# MDB.net
KiCad netlist of a schematic drawn in Altium Designer
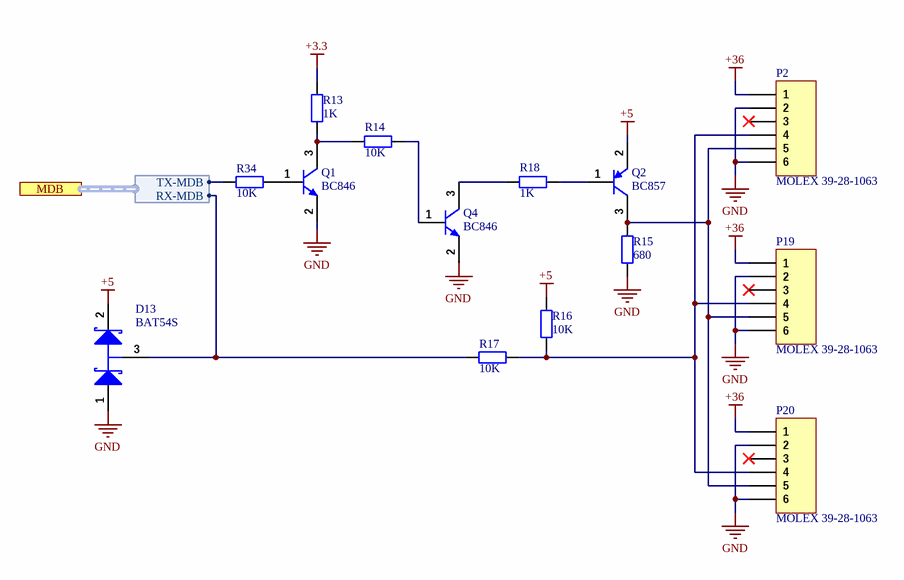
[diagram p0: MDB.SchDoc]

(export (version "E")
  (design (tool "Eeschema 10.0.6"))
  (components
    (comp (ref "D13")
      (value "BAT54S")
      (footprint "SOT23")
      (description "Schottky Barrier Double Diode")
      (fields (field (name "MANUFACTURER") "MULTICOMP"))
      (libsource (lib "Ares") (part "BAT54S"))
    )
    (comp (ref "P2")
      (value "MOLEX 39-28-1063")
      (footprint "MOLEX 39-28-1063")
      (description "Connecteur MDB")
      (fields (field (name "MANUFACTURER") "MOLEX") (field (name "MANUFACTURER PART NUMBER") "39-28-1063"))
      (libsource (lib "Miscellaneous Connectors") (part "Header 6"))
    )
    (comp (ref "P19")
      (value "MOLEX 39-28-1063")
      (footprint "MOLEX 39-28-1063")
      (description "Connecteur MDB")
      (fields (field (name "MANUFACTURER") "MOLEX") (field (name "MANUFACTURER PART NUMBER") "39-28-1063"))
      (libsource (lib "Miscellaneous Connectors") (part "Header 6"))
    )
    (comp (ref "P20")
      (value "MOLEX 39-28-1063")
      (footprint "MOLEX 39-28-1063")
      (description "Connecteur MDB")
      (fields (field (name "MANUFACTURER") "MOLEX") (field (name "MANUFACTURER PART NUMBER") "39-28-1063"))
      (libsource (lib "Miscellaneous Connectors") (part "Header 6"))
    )
    (comp (ref "Q1")
      (value "BC846")
      (footprint "SOT-23")
      (description "NPN General-purpose Transistor")
      (fields (field (name "MANUFACTURER") "NXP"))
      (libsource (lib "Philips Discrete BJT - Low Power") (part "BC846B"))
    )
    (comp (ref "Q2")
      (value "BC857")
      (footprint "SOT-23")
      (description "PNP Switching Transistor")
      (fields (field (name "MANUFACTURER") "NXP"))
      (libsource (lib "Philips Discrete BJT - Low Power") (part "PMBT2907A"))
    )
    (comp (ref "Q4")
      (value "BC846")
      (footprint "SOT-23")
      (description "NPN General-purpose Transistor")
      (fields (field (name "MANUFACTURER") "NXP"))
      (libsource (lib "Philips Discrete BJT - Low Power") (part "BC846B"))
    )
    (comp (ref "R13")
      (value "1K")
      (footprint "R0805")
      (description "Resistor")
      (fields
        (field (name "MANUFACTURER") "MULTICOMP")
        (field (name "MANUFACTURER PART NUMBER") "MC0.1W08051%1KFR")
      )
      (libsource (lib "BRA") (part "Resistor 0805 1K"))
    )
    (comp (ref "R14")
      (value "10K")
      (footprint "R0805")
      (description "Resistor")
      (fields
        (field (name "MANUFACTURER") "MULTICOMP")
        (field (name "MANUFACTURER PART NUMBER") "MC0.1W08051%10KFR")
      )
      (libsource (lib "BRA") (part "Resistor 0805 10K"))
    )
    (comp (ref "R15")
      (value "680")
      (footprint "R0805")
      (description "Resistor")
      (fields
        (field (name "MANUFACTURER") "MULTICOMP")
        (field (name "MANUFACTURER PART NUMBER") "MC01W08051680R")
      )
      (libsource (lib "BRA") (part "Resistor 0805 680"))
    )
    (comp (ref "R16")
      (value "10K")
      (footprint "R0805")
      (description "Resistor")
      (fields
        (field (name "MANUFACTURER") "MULTICOMP")
        (field (name "MANUFACTURER PART NUMBER") "MC01W0805110K")
      )
      (libsource (lib "BRA") (part "Resistor 0805 390"))
    )
    (comp (ref "R17")
      (value "10K")
      (footprint "R0805")
      (description "Resistor")
      (fields
        (field (name "MANUFACTURER") "MULTICOMP")
        (field (name "MANUFACTURER PART NUMBER") "MC0.1W08051%10KFR")
      )
      (libsource (lib "BRA") (part "Resistor 0805 10K"))
    )
    (comp (ref "R18")
      (value "1K")
      (footprint "R0805")
      (description "Resistor")
      (fields
        (field (name "MANUFACTURER") "MULTICOMP")
        (field (name "MANUFACTURER PART NUMBER") "MC0.1W08051%1KFR")
      )
      (libsource (lib "") (part "Resistor 0805 1K_1"))
    )
    (comp (ref "R34")
      (value "10K")
      (footprint "R0805")
      (description "Resistor")
      (fields
        (field (name "MANUFACTURER") "MULTICOMP")
        (field (name "MANUFACTURER PART NUMBER") "MC0.1W08051%10KFR")
      )
      (libsource (lib "BRA") (part "Resistor 0805 10K"))
    )
  )
  (nets
    (net (code "2") (name "+3.3") (class "Default")
      (node (ref "R13") (pin "2") (pinfunction "2_2") (pintype "passive"))
    )
    (net (code "3") (name "+5") (class "Default")
      (node (ref "D13") (pin "2") (pinfunction "K_2") (pintype "passive"))
      (node (ref "Q2") (pin "2") (pinfunction "E_2") (pintype "passive"))
      (node (ref "R16") (pin "2") (pinfunction "2_2") (pintype "passive"))
    )
    (net (code "4") (name "+36") (class "Default")
      (node (ref "P19") (pin "1") (pinfunction "1_1") (pintype "passive"))
      (node (ref "P2") (pin "1") (pinfunction "1_1") (pintype "passive"))
      (node (ref "P20") (pin "1") (pinfunction "1_1") (pintype "passive"))
    )
    (net (code "5") (name "/RX-MDB") (class "Default")
      (node (ref "D13") (pin "3") (pinfunction "C_3") (pintype "passive"))
      (node (ref "R17") (pin "2") (pinfunction "2_2") (pintype "passive"))
    )
    (net (code "6") (name "/TX-MDB") (class "Default")
      (node (ref "R34") (pin "2") (pinfunction "2_2") (pintype "passive"))
    )
    (net (code "8") (name "GND") (class "Default")
      (node (ref "D13") (pin "1") (pinfunction "A_1") (pintype "passive"))
      (node (ref "P19") (pin "2") (pinfunction "2_2") (pintype "passive"))
      (node (ref "P19") (pin "6") (pinfunction "6_6") (pintype "passive"))
      (node (ref "P2") (pin "2") (pinfunction "2_2") (pintype "passive"))
      (node (ref "P2") (pin "6") (pinfunction "6_6") (pintype "passive"))
      (node (ref "P20") (pin "2") (pinfunction "2_2") (pintype "passive"))
      (node (ref "P20") (pin "6") (pinfunction "6_6") (pintype "passive"))
      (node (ref "Q1") (pin "2") (pinfunction "E_2") (pintype "passive"))
      (node (ref "Q4") (pin "2") (pinfunction "E_2") (pintype "passive"))
      (node (ref "R15") (pin "1") (pinfunction "1_1") (pintype "passive"))
    )
    (net (code "9") (name "Net-(P19-Pad4)") (class "Default")
      (node (ref "P19") (pin "4") (pinfunction "4_4") (pintype "passive"))
      (node (ref "P2") (pin "4") (pinfunction "4_4") (pintype "passive"))
      (node (ref "P20") (pin "4") (pinfunction "4_4") (pintype "passive"))
      (node (ref "R16") (pin "1") (pinfunction "1_1") (pintype "passive"))
      (node (ref "R17") (pin "1") (pinfunction "1_1") (pintype "passive"))
    )
    (net (code "10") (name "Net-(Q1-B)") (class "Default")
      (node (ref "Q1") (pin "1") (pinfunction "B_1") (pintype "passive"))
      (node (ref "R34") (pin "1") (pinfunction "1_1") (pintype "passive"))
    )
    (net (code "11") (name "Net-(Q1-C)") (class "Default")
      (node (ref "Q1") (pin "3") (pinfunction "C_3") (pintype "passive"))
      (node (ref "R13") (pin "1") (pinfunction "1_1") (pintype "passive"))
      (node (ref "R14") (pin "2") (pinfunction "2_2") (pintype "passive"))
    )
    (net (code "12") (name "Net-(Q2-B)") (class "Default")
      (node (ref "Q2") (pin "1") (pinfunction "B_1") (pintype "passive"))
      (node (ref "R18") (pin "1") (pinfunction "1_1") (pintype "passive"))
    )
    (net (code "13") (name "Net-(Q2-C)") (class "Default")
      (node (ref "P19") (pin "5") (pinfunction "5_5") (pintype "passive"))
      (node (ref "P2") (pin "5") (pinfunction "5_5") (pintype "passive"))
      (node (ref "P20") (pin "5") (pinfunction "5_5") (pintype "passive"))
      (node (ref "Q2") (pin "3") (pinfunction "C_3") (pintype "passive"))
      (node (ref "R15") (pin "2") (pinfunction "2_2") (pintype "passive"))
    )
    (net (code "14") (name "Net-(Q4-B)") (class "Default")
      (node (ref "Q4") (pin "1") (pinfunction "B_1") (pintype "passive"))
      (node (ref "R14") (pin "1") (pinfunction "1_1") (pintype "passive"))
    )
    (net (code "15") (name "Net-(Q4-C)") (class "Default")
      (node (ref "Q4") (pin "3") (pinfunction "C_3") (pintype "passive"))
      (node (ref "R18") (pin "2") (pinfunction "2_2") (pintype "passive"))
    )
    (net (code "16") (name "unconnected-(P2-Pad3)") (class "Default")
      (node (ref "P2") (pin "3") (pinfunction "3_3") (pintype "passive+no_connect"))
    )
    (net (code "17") (name "unconnected-(P19-Pad3)") (class "Default")
      (node (ref "P19") (pin "3") (pinfunction "3_3") (pintype "passive+no_connect"))
    )
    (net (code "18") (name "unconnected-(P20-Pad3)") (class "Default")
      (node (ref "P20") (pin "3") (pinfunction "3_3") (pintype "passive+no_connect"))
    )
  )
)
